# axiom_beta_plugin_module_1xUSB30_v0_2_r1.net
KiCad netlist of a schematic drawn in EAGLE
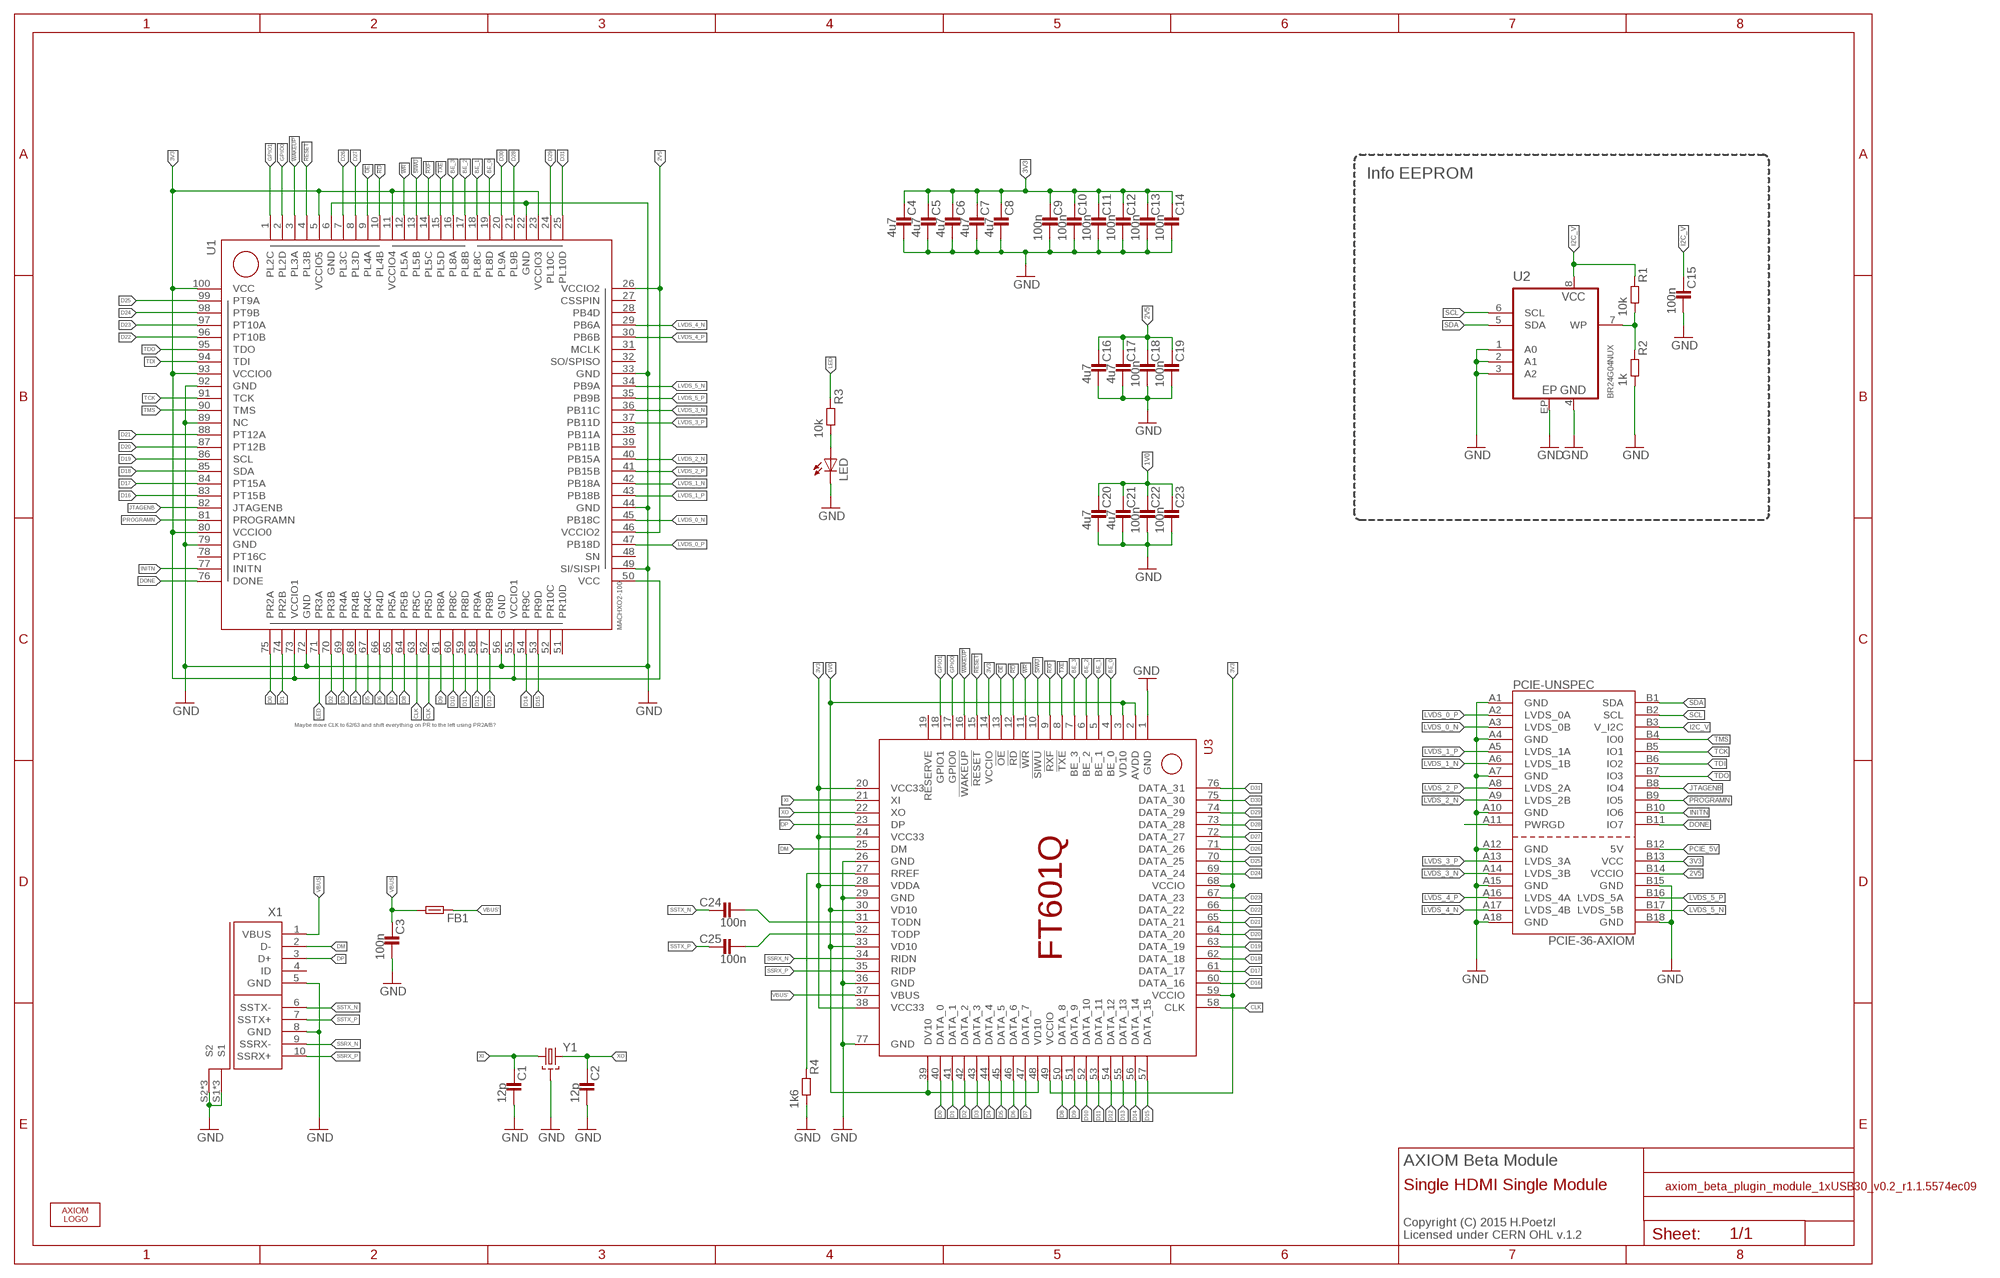
[diagram p0: schematic, sheet 1]

(export (version "E")
  (design (tool "Eeschema 10.0.6"))
  (components
    (comp (ref "C1")
      (value "12p")
      (footprint "eagle-import:0402-C")
      (libsource (lib "eagle-import") (part "C0402-C"))
    )
    (comp (ref "C2")
      (value "12p")
      (footprint "eagle-import:0402-C")
      (libsource (lib "eagle-import") (part "C0402-C"))
    )
    (comp (ref "C3")
      (value "100n")
      (footprint "eagle-import:0402-C")
      (libsource (lib "eagle-import") (part "C0402-C"))
    )
    (comp (ref "C4")
      (value "4u7")
      (footprint "eagle-import:0402-C")
      (libsource (lib "eagle-import") (part "C0402-C"))
    )
    (comp (ref "C5")
      (value "4u7")
      (footprint "eagle-import:0402-C")
      (libsource (lib "eagle-import") (part "C0402-C"))
    )
    (comp (ref "C6")
      (value "4u7")
      (footprint "eagle-import:0402-C")
      (libsource (lib "eagle-import") (part "C0402-C"))
    )
    (comp (ref "C7")
      (value "4u7")
      (footprint "eagle-import:0402-C")
      (libsource (lib "eagle-import") (part "C0402-C"))
    )
    (comp (ref "C8")
      (value "4u7")
      (footprint "eagle-import:0402-C")
      (libsource (lib "eagle-import") (part "C0402-C"))
    )
    (comp (ref "C9")
      (value "100n")
      (footprint "eagle-import:0402-C")
      (libsource (lib "eagle-import") (part "C0402-C"))
    )
    (comp (ref "C10")
      (value "100n")
      (footprint "eagle-import:0402-C")
      (libsource (lib "eagle-import") (part "C0402-C"))
    )
    (comp (ref "C11")
      (value "100n")
      (footprint "eagle-import:0402-C")
      (libsource (lib "eagle-import") (part "C0402-C"))
    )
    (comp (ref "C12")
      (value "100n")
      (footprint "eagle-import:0402-C")
      (libsource (lib "eagle-import") (part "C0402-C"))
    )
    (comp (ref "C13")
      (value "100n")
      (footprint "eagle-import:0402-C")
      (libsource (lib "eagle-import") (part "C0402-C"))
    )
    (comp (ref "C14")
      (value "100n")
      (footprint "eagle-import:0402-C")
      (libsource (lib "eagle-import") (part "C0402-C"))
    )
    (comp (ref "C15")
      (value "100n")
      (footprint "eagle-import:0402-C")
      (libsource (lib "eagle-import") (part "C0402-C"))
    )
    (comp (ref "C16")
      (value "4u7")
      (footprint "eagle-import:0402-C")
      (libsource (lib "eagle-import") (part "C0402-C"))
    )
    (comp (ref "C17")
      (value "4u7")
      (footprint "eagle-import:0402-C")
      (libsource (lib "eagle-import") (part "C0402-C"))
    )
    (comp (ref "C18")
      (value "100n")
      (footprint "eagle-import:0402-C")
      (libsource (lib "eagle-import") (part "C0402-C"))
    )
    (comp (ref "C19")
      (value "100n")
      (footprint "eagle-import:0402-C")
      (libsource (lib "eagle-import") (part "C0402-C"))
    )
    (comp (ref "C20")
      (value "4u7")
      (footprint "eagle-import:0402-C")
      (libsource (lib "eagle-import") (part "C0402-C"))
    )
    (comp (ref "C21")
      (value "4u7")
      (footprint "eagle-import:0402-C")
      (libsource (lib "eagle-import") (part "C0402-C"))
    )
    (comp (ref "C22")
      (value "100n")
      (footprint "eagle-import:0402-C")
      (libsource (lib "eagle-import") (part "C0402-C"))
    )
    (comp (ref "C23")
      (value "100n")
      (footprint "eagle-import:0402-C")
      (libsource (lib "eagle-import") (part "C0402-C"))
    )
    (comp (ref "C24")
      (value "100n")
      (footprint "eagle-import:0201-C")
      (libsource (lib "eagle-import") (part "C0201-C"))
    )
    (comp (ref "C25")
      (value "100n")
      (footprint "eagle-import:0201-C")
      (libsource (lib "eagle-import") (part "C0201-C"))
    )
    (comp (ref "FB1")
      (value "FB0402-C")
      (footprint "eagle-import:0402-C")
      (libsource (lib "eagle-import") (part "FB0402-C"))
    )
    (comp (ref "LED")
      (value "LED")
      (footprint "eagle-import:CHIPLED_0603")
      (libsource (lib "eagle-import") (part "LED"))
    )
    (comp (ref "PCIE-UNSPEC")
      (value "PCIE-36-AXIOM")
      (footprint "eagle-import:PCIE-36-AXIOM")
      (libsource (lib "eagle-import") (part "PCIE-36-AXIOM"))
    )
    (comp (ref "R1")
      (value "10k")
      (footprint "eagle-import:0402-C")
      (libsource (lib "eagle-import") (part "R0402-C"))
    )
    (comp (ref "R2")
      (value "1k")
      (footprint "eagle-import:0402-C")
      (libsource (lib "eagle-import") (part "R0402-C"))
    )
    (comp (ref "R3")
      (value "10k")
      (footprint "eagle-import:0402-B")
      (libsource (lib "eagle-import") (part "R0402-B"))
    )
    (comp (ref "R4")
      (value "1k6")
      (footprint "eagle-import:0201-C")
      (libsource (lib "eagle-import") (part "R0201-C"))
    )
    (comp (ref "U$")
      (value "AXIOM_LOGO328X50")
      (footprint "eagle-import:AXIOM_LOGO_328X50")
      (libsource (lib "eagle-import") (part "AXIOM_LOGO328X50"))
    )
    (comp (ref "U1")
      (value "MACHXO2-100")
      (footprint "eagle-import:MACHXO2-100TQFP")
      (libsource (lib "eagle-import") (part "MACHXO2-100"))
    )
    (comp (ref "U2")
      (value "BR24G04NUX")
      (footprint "eagle-import:DFN200X300X100-9N")
      (libsource (lib "eagle-import") (part "BR24G04NUX"))
    )
    (comp (ref "U3")
      (value "FT601QQFN76")
      (footprint "eagle-import:QFN76")
      (libsource (lib "eagle-import") (part "FT601QQFN76"))
    )
    (comp (ref "X1")
      (value "10_USB_3.0_2S-SMT")
      (footprint "eagle-import:MICRO-B-30-H-SMT")
      (libsource (lib "eagle-import") (part "10_USB_3.0_2S-SMT"))
    )
    (comp (ref "Y1")
      (value "SMD-4P-2G-2.0X1.6")
      (footprint "eagle-import:2.0X1.6")
      (libsource (lib "eagle-import") (part "SMD-4P-2G-2.0X1.6"))
    )
  )
  (nets
    (net (code "1") (name "/~{OE}") (class "Default")
      (node (ref "U1") (pin "9") (pinfunction "PL4A_9") (pintype "bidirectional"))
      (node (ref "U3") (pin "13") (pinfunction "~{OE}_13") (pintype "input"))
    )
    (net (code "2") (name "/~{RD}") (class "Default")
      (node (ref "U1") (pin "10") (pinfunction "PL4B_10") (pintype "bidirectional"))
      (node (ref "U3") (pin "12") (pinfunction "~{RD}_12") (pintype "input"))
    )
    (net (code "3") (name "/~{RESET}") (class "Default")
      (node (ref "U1") (pin "4") (pinfunction "PL3B_4") (pintype "bidirectional"))
      (node (ref "U3") (pin "15") (pinfunction "~{RESET}_15") (pintype "input"))
    )
    (net (code "4") (name "/~{RXF}") (class "Default")
      (node (ref "U1") (pin "14") (pinfunction "PL5C_14") (pintype "bidirectional"))
      (node (ref "U3") (pin "9") (pinfunction "~{RXF}_9") (pintype "output"))
    )
    (net (code "5") (name "/~{SIWU}") (class "Default")
      (node (ref "U1") (pin "13") (pinfunction "PL5B_13") (pintype "bidirectional"))
      (node (ref "U3") (pin "10") (pinfunction "~{SIWU}_10") (pintype "input"))
    )
    (net (code "6") (name "/~{TXE}") (class "Default")
      (node (ref "U1") (pin "15") (pinfunction "PL5D_15") (pintype "bidirectional"))
      (node (ref "U3") (pin "8") (pinfunction "~{TXE}_8") (pintype "output"))
    )
    (net (code "7") (name "/~{WAKEUP}") (class "Default")
      (node (ref "U1") (pin "3") (pinfunction "PL3A_3") (pintype "bidirectional"))
      (node (ref "U3") (pin "16") (pinfunction "~{WAKEUP}_16") (pintype "bidirectional"))
    )
    (net (code "8") (name "/~{WR}") (class "Default")
      (node (ref "U1") (pin "12") (pinfunction "PL5A_12") (pintype "bidirectional"))
      (node (ref "U3") (pin "11") (pinfunction "~{WR}_11") (pintype "input"))
    )
    (net (code "9") (name "1V0") (class "Default")
      (node (ref "C20") (pin "1") (pinfunction "1_1") (pintype "passive"))
      (node (ref "C21") (pin "1") (pinfunction "1_1") (pintype "passive"))
      (node (ref "C22") (pin "1") (pinfunction "1_1") (pintype "passive"))
      (node (ref "C23") (pin "1") (pinfunction "1_1") (pintype "passive"))
      (node (ref "U3") (pin "2") (pinfunction "AVDD_2") (pintype "power_in"))
      (node (ref "U3") (pin "3") (pinfunction "VD10_3") (pintype "power_in"))
      (node (ref "U3") (pin "30") (pinfunction "VD10_30") (pintype "power_in"))
      (node (ref "U3") (pin "33") (pinfunction "VD10_33") (pintype "power_in"))
      (node (ref "U3") (pin "39") (pinfunction "DV10_39") (pintype "power_in"))
      (node (ref "U3") (pin "48") (pinfunction "VD10_48") (pintype "power_in"))
    )
    (net (code "10") (name "2V5") (class "Default")
      (node (ref "C16") (pin "1") (pinfunction "1_1") (pintype "passive"))
      (node (ref "C17") (pin "1") (pinfunction "1_1") (pintype "passive"))
      (node (ref "C18") (pin "1") (pinfunction "1_1") (pintype "passive"))
      (node (ref "C19") (pin "1") (pinfunction "1_1") (pintype "passive"))
      (node (ref "PCIE-UNSPEC") (pin "B14") (pinfunction "VCCIO_B14") (pintype "passive"))
      (node (ref "U1") (pin "26") (pinfunction "VCCIO2_26") (pintype "power_in"))
      (node (ref "U1") (pin "46") (pinfunction "VCCIO2_46") (pintype "power_in"))
    )
    (net (code "11") (name "3V3") (class "Default")
      (node (ref "C10") (pin "1") (pinfunction "1_1") (pintype "passive"))
      (node (ref "C11") (pin "1") (pinfunction "1_1") (pintype "passive"))
      (node (ref "C12") (pin "1") (pinfunction "1_1") (pintype "passive"))
      (node (ref "C13") (pin "1") (pinfunction "1_1") (pintype "passive"))
      (node (ref "C14") (pin "1") (pinfunction "1_1") (pintype "passive"))
      (node (ref "C4") (pin "1") (pinfunction "1_1") (pintype "passive"))
      (node (ref "C5") (pin "1") (pinfunction "1_1") (pintype "passive"))
      (node (ref "C6") (pin "1") (pinfunction "1_1") (pintype "passive"))
      (node (ref "C7") (pin "1") (pinfunction "1_1") (pintype "passive"))
      (node (ref "C8") (pin "1") (pinfunction "1_1") (pintype "passive"))
      (node (ref "C9") (pin "1") (pinfunction "1_1") (pintype "passive"))
      (node (ref "PCIE-UNSPEC") (pin "B13") (pinfunction "VCC_B13") (pintype "passive"))
      (node (ref "U1") (pin "100") (pinfunction "VCC_100") (pintype "power_in"))
      (node (ref "U1") (pin "11") (pinfunction "VCCIO4_11") (pintype "power_in"))
      (node (ref "U1") (pin "23") (pinfunction "VCCIO3_23") (pintype "power_in"))
      (node (ref "U1") (pin "5") (pinfunction "VCCIO5_5") (pintype "power_in"))
      (node (ref "U1") (pin "50") (pinfunction "VCC_50") (pintype "power_in"))
      (node (ref "U1") (pin "55") (pinfunction "VCCIO1_55") (pintype "power_in"))
      (node (ref "U1") (pin "73") (pinfunction "VCCIO1_73") (pintype "power_in"))
      (node (ref "U1") (pin "80") (pinfunction "VCCIO0_80") (pintype "power_in"))
      (node (ref "U1") (pin "93") (pinfunction "VCCIO0_93") (pintype "power_in"))
      (node (ref "U3") (pin "14") (pinfunction "VCCIO_14") (pintype "power_in"))
      (node (ref "U3") (pin "20") (pinfunction "VCC33_20") (pintype "power_in"))
      (node (ref "U3") (pin "24") (pinfunction "VCC33_24") (pintype "power_in"))
      (node (ref "U3") (pin "28") (pinfunction "VDDA_28") (pintype "bidirectional"))
      (node (ref "U3") (pin "38") (pinfunction "VCC33_38") (pintype "power_in"))
      (node (ref "U3") (pin "49") (pinfunction "VCCIO_49") (pintype "power_in"))
      (node (ref "U3") (pin "59") (pinfunction "VCCIO_59") (pintype "power_in"))
      (node (ref "U3") (pin "68") (pinfunction "VCCIO_68") (pintype "power_in"))
    )
    (net (code "12") (name "BE_0") (class "Default")
      (node (ref "U1") (pin "19") (pinfunction "PL8D_19") (pintype "bidirectional"))
      (node (ref "U3") (pin "4") (pinfunction "BE_0_4") (pintype "bidirectional"))
    )
    (net (code "13") (name "BE_1") (class "Default")
      (node (ref "U1") (pin "18") (pinfunction "PL8C_18") (pintype "bidirectional"))
      (node (ref "U3") (pin "5") (pinfunction "BE_1_5") (pintype "bidirectional"))
    )
    (net (code "14") (name "BE_2") (class "Default")
      (node (ref "U1") (pin "17") (pinfunction "PL8B_17") (pintype "bidirectional"))
      (node (ref "U3") (pin "6") (pinfunction "BE_2_6") (pintype "bidirectional"))
    )
    (net (code "15") (name "BE_3") (class "Default")
      (node (ref "U1") (pin "16") (pinfunction "PL8A_16") (pintype "bidirectional"))
      (node (ref "U3") (pin "7") (pinfunction "BE_3_7") (pintype "bidirectional"))
    )
    (net (code "16") (name "CLK") (class "Default")
      (node (ref "U1") (pin "62") (pinfunction "PR5D_62") (pintype "bidirectional"))
      (node (ref "U1") (pin "63") (pinfunction "PR5C_63") (pintype "bidirectional"))
      (node (ref "U3") (pin "58") (pinfunction "CLK_58") (pintype "output"))
    )
    (net (code "17") (name "D0") (class "Default")
      (node (ref "U1") (pin "75") (pinfunction "PR2A_75") (pintype "bidirectional"))
      (node (ref "U3") (pin "40") (pinfunction "DATA_0_40") (pintype "bidirectional"))
    )
    (net (code "18") (name "D1") (class "Default")
      (node (ref "U1") (pin "74") (pinfunction "PR2B_74") (pintype "bidirectional"))
      (node (ref "U3") (pin "41") (pinfunction "DATA_1_41") (pintype "bidirectional"))
    )
    (net (code "19") (name "D2") (class "Default")
      (node (ref "U1") (pin "70") (pinfunction "PR3B_70") (pintype "bidirectional"))
      (node (ref "U3") (pin "42") (pinfunction "DATA_2_42") (pintype "bidirectional"))
    )
    (net (code "20") (name "D3") (class "Default")
      (node (ref "U1") (pin "69") (pinfunction "PR4A_69") (pintype "bidirectional"))
      (node (ref "U3") (pin "43") (pinfunction "DATA_3_43") (pintype "bidirectional"))
    )
    (net (code "21") (name "D4") (class "Default")
      (node (ref "U1") (pin "68") (pinfunction "PR4B_68") (pintype "bidirectional"))
      (node (ref "U3") (pin "44") (pinfunction "DATA_4_44") (pintype "bidirectional"))
    )
    (net (code "22") (name "D5") (class "Default")
      (node (ref "U1") (pin "67") (pinfunction "PR4C_67") (pintype "bidirectional"))
      (node (ref "U3") (pin "45") (pinfunction "DATA_5_45") (pintype "bidirectional"))
    )
    (net (code "23") (name "D6") (class "Default")
      (node (ref "U1") (pin "66") (pinfunction "PR4D_66") (pintype "bidirectional"))
      (node (ref "U3") (pin "46") (pinfunction "DATA_6_46") (pintype "bidirectional"))
    )
    (net (code "24") (name "D7") (class "Default")
      (node (ref "U1") (pin "65") (pinfunction "PR5A_65") (pintype "bidirectional"))
      (node (ref "U3") (pin "47") (pinfunction "DATA_7_47") (pintype "bidirectional"))
    )
    (net (code "25") (name "D8") (class "Default")
      (node (ref "U1") (pin "64") (pinfunction "PR5B_64") (pintype "bidirectional"))
      (node (ref "U3") (pin "50") (pinfunction "DATA_8_50") (pintype "bidirectional"))
    )
    (net (code "26") (name "D9") (class "Default")
      (node (ref "U1") (pin "61") (pinfunction "PR8A_61") (pintype "bidirectional"))
      (node (ref "U3") (pin "51") (pinfunction "DATA_9_51") (pintype "bidirectional"))
    )
    (net (code "27") (name "D10") (class "Default")
      (node (ref "U1") (pin "60") (pinfunction "PR8C_60") (pintype "bidirectional"))
      (node (ref "U3") (pin "52") (pinfunction "DATA_10_52") (pintype "bidirectional"))
    )
    (net (code "28") (name "D11") (class "Default")
      (node (ref "U1") (pin "59") (pinfunction "PR8D_59") (pintype "bidirectional"))
      (node (ref "U3") (pin "53") (pinfunction "DATA_11_53") (pintype "bidirectional"))
    )
    (net (code "29") (name "D12") (class "Default")
      (node (ref "U1") (pin "58") (pinfunction "PR9A_58") (pintype "bidirectional"))
      (node (ref "U3") (pin "54") (pinfunction "DATA_12_54") (pintype "bidirectional"))
    )
    (net (code "30") (name "D13") (class "Default")
      (node (ref "U1") (pin "57") (pinfunction "PR9B_57") (pintype "bidirectional"))
      (node (ref "U3") (pin "55") (pinfunction "DATA_13_55") (pintype "bidirectional"))
    )
    (net (code "31") (name "D14") (class "Default")
      (node (ref "U1") (pin "54") (pinfunction "PR9C_54") (pintype "bidirectional"))
      (node (ref "U3") (pin "56") (pinfunction "DATA_14_56") (pintype "bidirectional"))
    )
    (net (code "32") (name "D15") (class "Default")
      (node (ref "U1") (pin "53") (pinfunction "PR9D_53") (pintype "bidirectional"))
      (node (ref "U3") (pin "57") (pinfunction "DATA_15_57") (pintype "bidirectional"))
    )
    (net (code "33") (name "D16") (class "Default")
      (node (ref "U1") (pin "83") (pinfunction "PT15B_83") (pintype "bidirectional"))
      (node (ref "U3") (pin "60") (pinfunction "DATA_16_60") (pintype "bidirectional"))
    )
    (net (code "34") (name "D17") (class "Default")
      (node (ref "U1") (pin "84") (pinfunction "PT15A_84") (pintype "bidirectional"))
      (node (ref "U3") (pin "61") (pinfunction "DATA_17_61") (pintype "bidirectional"))
    )
    (net (code "35") (name "D18") (class "Default")
      (node (ref "U1") (pin "85") (pinfunction "SDA_85") (pintype "bidirectional"))
      (node (ref "U3") (pin "62") (pinfunction "DATA_18_62") (pintype "bidirectional"))
    )
    (net (code "36") (name "D19") (class "Default")
      (node (ref "U1") (pin "86") (pinfunction "SCL_86") (pintype "bidirectional"))
      (node (ref "U3") (pin "63") (pinfunction "DATA_19_63") (pintype "bidirectional"))
    )
    (net (code "37") (name "D20") (class "Default")
      (node (ref "U1") (pin "87") (pinfunction "PT12B_87") (pintype "bidirectional"))
      (node (ref "U3") (pin "64") (pinfunction "DATA_20_64") (pintype "bidirectional"))
    )
    (net (code "38") (name "D21") (class "Default")
      (node (ref "U1") (pin "88") (pinfunction "PT12A_88") (pintype "bidirectional"))
      (node (ref "U3") (pin "65") (pinfunction "DATA_21_65") (pintype "bidirectional"))
    )
    (net (code "39") (name "D22") (class "Default")
      (node (ref "U1") (pin "96") (pinfunction "PT10B_96") (pintype "bidirectional"))
      (node (ref "U3") (pin "66") (pinfunction "DATA_22_66") (pintype "bidirectional"))
    )
    (net (code "40") (name "D23") (class "Default")
      (node (ref "U1") (pin "97") (pinfunction "PT10A_97") (pintype "bidirectional"))
      (node (ref "U3") (pin "67") (pinfunction "DATA_23_67") (pintype "bidirectional"))
    )
    (net (code "41") (name "D24") (class "Default")
      (node (ref "U1") (pin "98") (pinfunction "PT9B_98") (pintype "bidirectional"))
      (node (ref "U3") (pin "69") (pinfunction "DATA_24_69") (pintype "bidirectional"))
    )
    (net (code "42") (name "D25") (class "Default")
      (node (ref "U1") (pin "99") (pinfunction "PT9A_99") (pintype "bidirectional"))
      (node (ref "U3") (pin "70") (pinfunction "DATA_25_70") (pintype "bidirectional"))
    )
    (net (code "43") (name "D26") (class "Default")
      (node (ref "U1") (pin "7") (pinfunction "PL3C_7") (pintype "bidirectional"))
      (node (ref "U3") (pin "71") (pinfunction "DATA_26_71") (pintype "bidirectional"))
    )
    (net (code "44") (name "D27") (class "Default")
      (node (ref "U1") (pin "8") (pinfunction "PL3D_8") (pintype "bidirectional"))
      (node (ref "U3") (pin "72") (pinfunction "DATA_27_72") (pintype "bidirectional"))
    )
    (net (code "45") (name "D28") (class "Default")
      (node (ref "U1") (pin "21") (pinfunction "PL9B_21") (pintype "bidirectional"))
      (node (ref "U3") (pin "73") (pinfunction "DATA_28_73") (pintype "bidirectional"))
    )
    (net (code "46") (name "D29") (class "Default")
      (node (ref "U1") (pin "24") (pinfunction "PL10C_24") (pintype "bidirectional"))
      (node (ref "U3") (pin "74") (pinfunction "DATA_29_74") (pintype "bidirectional"))
    )
    (net (code "47") (name "D30") (class "Default")
      (node (ref "U1") (pin "20") (pinfunction "PL9A_20") (pintype "bidirectional"))
      (node (ref "U3") (pin "75") (pinfunction "DATA_30_75") (pintype "bidirectional"))
    )
    (net (code "48") (name "D31") (class "Default")
      (node (ref "U1") (pin "25") (pinfunction "PL10D_25") (pintype "bidirectional"))
      (node (ref "U3") (pin "76") (pinfunction "DATA_31_76") (pintype "bidirectional"))
    )
    (net (code "49") (name "DM") (class "Default")
      (node (ref "U3") (pin "25") (pinfunction "DM_25") (pintype "bidirectional"))
      (node (ref "X1") (pin "2") (pinfunction "D-_2") (pintype "passive"))
    )
    (net (code "50") (name "DONE") (class "Default")
      (node (ref "PCIE-UNSPEC") (pin "B11") (pinfunction "IO7_B11") (pintype "passive"))
      (node (ref "U1") (pin "76") (pinfunction "DONE_76") (pintype "bidirectional"))
    )
    (net (code "51") (name "DP") (class "Default")
      (node (ref "U3") (pin "23") (pinfunction "DP_23") (pintype "bidirectional"))
      (node (ref "X1") (pin "3") (pinfunction "D+_3") (pintype "passive"))
    )
    (net (code "52") (name "GND") (class "Default")
      (node (ref "C1") (pin "2") (pinfunction "2_2") (pintype "passive"))
      (node (ref "C10") (pin "2") (pinfunction "2_2") (pintype "passive"))
      (node (ref "C11") (pin "2") (pinfunction "2_2") (pintype "passive"))
      (node (ref "C12") (pin "2") (pinfunction "2_2") (pintype "passive"))
      (node (ref "C13") (pin "2") (pinfunction "2_2") (pintype "passive"))
      (node (ref "C14") (pin "2") (pinfunction "2_2") (pintype "passive"))
      (node (ref "C15") (pin "2") (pinfunction "2_2") (pintype "passive"))
      (node (ref "C16") (pin "2") (pinfunction "2_2") (pintype "passive"))
      (node (ref "C17") (pin "2") (pinfunction "2_2") (pintype "passive"))
      (node (ref "C18") (pin "2") (pinfunction "2_2") (pintype "passive"))
      (node (ref "C19") (pin "2") (pinfunction "2_2") (pintype "passive"))
      (node (ref "C2") (pin "2") (pinfunction "2_2") (pintype "passive"))
      (node (ref "C20") (pin "2") (pinfunction "2_2") (pintype "passive"))
      (node (ref "C21") (pin "2") (pinfunction "2_2") (pintype "passive"))
      (node (ref "C22") (pin "2") (pinfunction "2_2") (pintype "passive"))
      (node (ref "C23") (pin "2") (pinfunction "2_2") (pintype "passive"))
      (node (ref "C3") (pin "2") (pinfunction "2_2") (pintype "passive"))
      (node (ref "C4") (pin "2") (pinfunction "2_2") (pintype "passive"))
      (node (ref "C5") (pin "2") (pinfunction "2_2") (pintype "passive"))
      (node (ref "C6") (pin "2") (pinfunction "2_2") (pintype "passive"))
      (node (ref "C7") (pin "2") (pinfunction "2_2") (pintype "passive"))
      (node (ref "C8") (pin "2") (pinfunction "2_2") (pintype "passive"))
      (node (ref "C9") (pin "2") (pinfunction "2_2") (pintype "passive"))
      (node (ref "LED") (pin "C") (pinfunction "C_C") (pintype "passive"))
      (node (ref "PCIE-UNSPEC") (pin "A1") (pinfunction "GND_A1") (pintype "passive"))
      (node (ref "PCIE-UNSPEC") (pin "A10") (pinfunction "GND_A10") (pintype "passive"))
      (node (ref "PCIE-UNSPEC") (pin "A12") (pinfunction "GND_A12") (pintype "passive"))
      (node (ref "PCIE-UNSPEC") (pin "A15") (pinfunction "GND_A15") (pintype "passive"))
      (node (ref "PCIE-UNSPEC") (pin "A18") (pinfunction "GND_A18") (pintype "passive"))
      (node (ref "PCIE-UNSPEC") (pin "A4") (pinfunction "GND_A4") (pintype "passive"))
      (node (ref "PCIE-UNSPEC") (pin "A7") (pinfunction "GND_A7") (pintype "passive"))
      (node (ref "PCIE-UNSPEC") (pin "B15") (pinfunction "GND_B15") (pintype "passive"))
      (node (ref "PCIE-UNSPEC") (pin "B18") (pinfunction "GND_B18") (pintype "passive"))
      (node (ref "R2") (pin "2") (pinfunction "2_2") (pintype "passive"))
      (node (ref "R4") (pin "2") (pinfunction "2_2") (pintype "passive"))
      (node (ref "U1") (pin "22") (pinfunction "GND_22") (pintype "power_in"))
      (node (ref "U1") (pin "33") (pinfunction "GND_33") (pintype "power_in"))
      (node (ref "U1") (pin "44") (pinfunction "GND_44") (pintype "power_in"))
      (node (ref "U1") (pin "49") (pinfunction "SI/SISPI_49") (pintype "bidirectional"))
      (node (ref "U1") (pin "56") (pinfunction "GND_56") (pintype "power_in"))
      (node (ref "U1") (pin "6") (pinfunction "GND_6") (pintype "power_in"))
      (node (ref "U1") (pin "72") (pinfunction "GND_72") (pintype "power_in"))
      (node (ref "U1") (pin "79") (pinfunction "GND_79") (pintype "power_in"))
      (node (ref "U1") (pin "89") (pinfunction "NC_89") (pintype "bidirectional"))
      (node (ref "U1") (pin "92") (pinfunction "GND_92") (pintype "power_in"))
      (node (ref "U2") (pin "1") (pinfunction "A0_1") (pintype "input"))
      (node (ref "U2") (pin "2") (pinfunction "A1_2") (pintype "input"))
      (node (ref "U2") (pin "3") (pinfunction "A2_3") (pintype "input"))
      (node (ref "U2") (pin "4") (pinfunction "GND_4") (pintype "passive"))
      (node (ref "U2") (pin "EP") (pinfunction "EP_EP") (pintype "passive"))
      (node (ref "U3") (pin "1") (pinfunction "GND_1") (pintype "power_in"))
      (node (ref "U3") (pin "26") (pinfunction "GND_26") (pintype "power_in"))
      (node (ref "U3") (pin "29") (pinfunction "GND_29") (pintype "power_in"))
      (node (ref "U3") (pin "36") (pinfunction "GND_36") (pintype "power_in"))
      (node (ref "U3") (pin "77") (pinfunction "GND_77") (pintype "power_in"))
      (node (ref "X1") (pin "5") (pinfunction "GND_5") (pintype "passive"))
      (node (ref "X1") (pin "8") (pinfunction "GND_8") (pintype "passive"))
      (node (ref "X1") (pin "S1") (pinfunction "S1_S1") (pintype "passive"))
      (node (ref "X1") (pin "S2") (pinfunction "S2_S2") (pintype "passive"))
      (node (ref "X1") (pin "Z1") (pinfunction "S1_Z1") (pintype "passive"))
      (node (ref "X1") (pin "Z2") (pinfunction "S1_Z2") (pintype "passive"))
      (node (ref "X1") (pin "Z3") (pinfunction "S2_Z3") (pintype "passive"))
      (node (ref "X1") (pin "Z4") (pinfunction "S2_Z4") (pintype "passive"))
      (node (ref "Y1") (pin "2") (pinfunction "GND_2") (pintype "power_in"))
      (node (ref "Y1") (pin "4") (pinfunction "GND_4") (pintype "power_in"))
    )
    (net (code "53") (name "GPIO0") (class "Default")
      (node (ref "U1") (pin "2") (pinfunction "PL2D_2") (pintype "bidirectional"))
      (node (ref "U3") (pin "17") (pinfunction "GPIO0_17") (pintype "bidirectional"))
    )
    (net (code "54") (name "GPIO1") (class "Default")
      (node (ref "U1") (pin "1") (pinfunction "PL2C_1") (pintype "bidirectional"))
      (node (ref "U3") (pin "18") (pinfunction "GPIO1_18") (pintype "bidirectional"))
    )
    (net (code "55") (name "I2C_V") (class "Default")
      (node (ref "C15") (pin "1") (pinfunction "1_1") (pintype "passive"))
      (node (ref "PCIE-UNSPEC") (pin "B3") (pinfunction "V_I2C_B3") (pintype "passive"))
      (node (ref "R1") (pin "1") (pinfunction "1_1") (pintype "passive"))
      (node (ref "U2") (pin "8") (pinfunction "VCC_8") (pintype "power_in"))
    )
    (net (code "56") (name "INITN") (class "Default")
      (node (ref "PCIE-UNSPEC") (pin "B10") (pinfunction "IO6_B10") (pintype "passive"))
      (node (ref "U1") (pin "77") (pinfunction "INITN_77") (pintype "bidirectional"))
    )
    (net (code "57") (name "JTAGENB") (class "Default")
      (node (ref "PCIE-UNSPEC") (pin "B8") (pinfunction "IO4_B8") (pintype "passive"))
      (node (ref "U1") (pin "82") (pinfunction "JTAGENB_82") (pintype "bidirectional"))
    )
    (net (code "58") (name "LED") (class "Default")
      (node (ref "R3") (pin "1") (pinfunction "1_1") (pintype "passive"))
      (node (ref "U1") (pin "71") (pinfunction "PR3A_71") (pintype "bidirectional"))
    )
    (net (code "59") (name "LVDS_0_N") (class "Default")
      (node (ref "PCIE-UNSPEC") (pin "A3") (pinfunction "LVDS_0B_A3") (pintype "passive"))
      (node (ref "U1") (pin "45") (pinfunction "PB18C_45") (pintype "bidirectional"))
    )
    (net (code "60") (name "LVDS_0_P") (class "Default")
      (node (ref "PCIE-UNSPEC") (pin "A2") (pinfunction "LVDS_0A_A2") (pintype "passive"))
      (node (ref "U1") (pin "47") (pinfunction "PB18D_47") (pintype "bidirectional"))
    )
    (net (code "61") (name "LVDS_1_N") (class "Default")
      (node (ref "PCIE-UNSPEC") (pin "A6") (pinfunction "LVDS_1B_A6") (pintype "passive"))
      (node (ref "U1") (pin "42") (pinfunction "PB18A_42") (pintype "bidirectional"))
    )
    (net (code "62") (name "LVDS_1_P") (class "Default")
      (node (ref "PCIE-UNSPEC") (pin "A5") (pinfunction "LVDS_1A_A5") (pintype "passive"))
      (node (ref "U1") (pin "43") (pinfunction "PB18B_43") (pintype "bidirectional"))
    )
    (net (code "63") (name "LVDS_2_N") (class "Default")
      (node (ref "PCIE-UNSPEC") (pin "A9") (pinfunction "LVDS_2B_A9") (pintype "passive"))
      (node (ref "U1") (pin "40") (pinfunction "PB15A_40") (pintype "bidirectional"))
    )
    (net (code "64") (name "LVDS_2_P") (class "Default")
      (node (ref "PCIE-UNSPEC") (pin "A8") (pinfunction "LVDS_2A_A8") (pintype "passive"))
      (node (ref "U1") (pin "41") (pinfunction "PB15B_41") (pintype "bidirectional"))
    )
    (net (code "65") (name "LVDS_3_N") (class "Default")
      (node (ref "PCIE-UNSPEC") (pin "A14") (pinfunction "LVDS_3B_A14") (pintype "passive"))
      (node (ref "U1") (pin "36") (pinfunction "PB11C_36") (pintype "bidirectional"))
    )
    (net (code "66") (name "LVDS_3_P") (class "Default")
      (node (ref "PCIE-UNSPEC") (pin "A13") (pinfunction "LVDS_3A_A13") (pintype "passive"))
      (node (ref "U1") (pin "37") (pinfunction "PB11D_37") (pintype "bidirectional"))
    )
    (net (code "67") (name "LVDS_4_N") (class "Default")
      (node (ref "PCIE-UNSPEC") (pin "A17") (pinfunction "LVDS_4B_A17") (pintype "passive"))
      (node (ref "U1") (pin "29") (pinfunction "PB6A_29") (pintype "bidirectional"))
    )
    (net (code "68") (name "LVDS_4_P") (class "Default")
      (node (ref "PCIE-UNSPEC") (pin "A16") (pinfunction "LVDS_4A_A16") (pintype "passive"))
      (node (ref "U1") (pin "30") (pinfunction "PB6B_30") (pintype "bidirectional"))
    )
    (net (code "69") (name "LVDS_5_N") (class "Default")
      (node (ref "PCIE-UNSPEC") (pin "B17") (pinfunction "LVDS_5B_B17") (pintype "passive"))
      (node (ref "U1") (pin "34") (pinfunction "PB9A_34") (pintype "bidirectional"))
    )
    (net (code "70") (name "LVDS_5_P") (class "Default")
      (node (ref "PCIE-UNSPEC") (pin "B16") (pinfunction "LVDS_5A_B16") (pintype "passive"))
      (node (ref "U1") (pin "35") (pinfunction "PB9B_35") (pintype "bidirectional"))
    )
    (net (code "71") (name "Net-(LED-PadA)") (class "Default")
      (node (ref "LED") (pin "A") (pinfunction "A_A") (pintype "passive"))
      (node (ref "R3") (pin "2") (pinfunction "2_2") (pintype "passive"))
    )
    (net (code "72") (name "Net-(U2-WP)") (class "Default")
      (node (ref "R1") (pin "2") (pinfunction "2_2") (pintype "passive"))
      (node (ref "R2") (pin "1") (pinfunction "1_1") (pintype "passive"))
      (node (ref "U2") (pin "7") (pinfunction "WP_7") (pintype "input"))
    )
    (net (code "73") (name "Net-(U3-RREF)") (class "Default")
      (node (ref "R4") (pin "1") (pinfunction "1_1") (pintype "passive"))
      (node (ref "U3") (pin "27") (pinfunction "RREF_27") (pintype "input"))
    )
    (net (code "74") (name "Net-(U3-TODN)") (class "Default")
      (node (ref "C24") (pin "2") (pinfunction "2_2") (pintype "passive"))
      (node (ref "U3") (pin "31") (pinfunction "TODN_31") (pintype "output"))
    )
    (net (code "75") (name "Net-(U3-TODP)") (class "Default")
      (node (ref "C25") (pin "2") (pinfunction "2_2") (pintype "passive"))
      (node (ref "U3") (pin "32") (pinfunction "TODP_32") (pintype "output"))
    )
    (net (code "76") (name "PCIE_5V") (class "Default")
      (node (ref "PCIE-UNSPEC") (pin "B12") (pinfunction "5V_B12") (pintype "passive"))
    )
    (net (code "77") (name "PROGRAMN") (class "Default")
      (node (ref "PCIE-UNSPEC") (pin "B9") (pinfunction "IO5_B9") (pintype "passive"))
      (node (ref "U1") (pin "81") (pinfunction "PROGRAMN_81") (pintype "bidirectional"))
    )
    (net (code "78") (name "SCL") (class "Default")
      (node (ref "PCIE-UNSPEC") (pin "B2") (pinfunction "SCL_B2") (pintype "passive"))
      (node (ref "U2") (pin "6") (pinfunction "SCL_6") (pintype "input"))
    )
    (net (code "79") (name "SDA") (class "Default")
      (node (ref "PCIE-UNSPEC") (pin "B1") (pinfunction "SDA_B1") (pintype "passive"))
      (node (ref "U2") (pin "5") (pinfunction "SDA_5") (pintype "bidirectional"))
    )
    (net (code "80") (name "SSRX_N") (class "Default")
      (node (ref "U3") (pin "34") (pinfunction "RIDN_34") (pintype "input"))
      (node (ref "X1") (pin "9") (pinfunction "SSRX-_9") (pintype "passive"))
    )
    (net (code "81") (name "SSRX_P") (class "Default")
      (node (ref "U3") (pin "35") (pinfunction "RIDP_35") (pintype "input"))
      (node (ref "X1") (pin "10") (pinfunction "SSRX+_10") (pintype "passive"))
    )
    (net (code "82") (name "SSTX_N") (class "Default")
      (node (ref "C24") (pin "1") (pinfunction "1_1") (pintype "passive"))
      (node (ref "X1") (pin "6") (pinfunction "SSTX-_6") (pintype "passive"))
    )
    (net (code "83") (name "SSTX_P") (class "Default")
      (node (ref "C25") (pin "1") (pinfunction "1_1") (pintype "passive"))
      (node (ref "X1") (pin "7") (pinfunction "SSTX+_7") (pintype "passive"))
    )
    (net (code "84") (name "TCK") (class "Default")
      (node (ref "PCIE-UNSPEC") (pin "B5") (pinfunction "IO1_B5") (pintype "passive"))
      (node (ref "U1") (pin "91") (pinfunction "TCK_91") (pintype "bidirectional"))
    )
    (net (code "85") (name "TDI") (class "Default")
      (node (ref "PCIE-UNSPEC") (pin "B6") (pinfunction "IO2_B6") (pintype "passive"))
      (node (ref "U1") (pin "94") (pinfunction "TDI_94") (pintype "bidirectional"))
    )
    (net (code "86") (name "TDO") (class "Default")
      (node (ref "PCIE-UNSPEC") (pin "B7") (pinfunction "IO3_B7") (pintype "passive"))
      (node (ref "U1") (pin "95") (pinfunction "TDO_95") (pintype "bidirectional"))
    )
    (net (code "87") (name "TMS") (class "Default")
      (node (ref "PCIE-UNSPEC") (pin "B4") (pinfunction "IO0_B4") (pintype "passive"))
      (node (ref "U1") (pin "90") (pinfunction "TMS_90") (pintype "bidirectional"))
    )
    (net (code "88") (name "VBUS") (class "Default")
      (node (ref "C3") (pin "1") (pinfunction "1_1") (pintype "passive"))
      (node (ref "FB1") (pin "2") (pinfunction "2_2") (pintype "passive"))
      (node (ref "X1") (pin "1") (pinfunction "VBUS_1") (pintype "passive"))
    )
    (net (code "89") (name "VBUS'") (class "Default")
      (node (ref "FB1") (pin "1") (pinfunction "1_1") (pintype "passive"))
      (node (ref "U3") (pin "37") (pinfunction "VBUS_37") (pintype "power_in"))
    )
    (net (code "90") (name "XI") (class "Default")
      (node (ref "C1") (pin "1") (pinfunction "1_1") (pintype "passive"))
      (node (ref "U3") (pin "21") (pinfunction "XI_21") (pintype "input"))
      (node (ref "Y1") (pin "1") (pinfunction "1_1") (pintype "passive"))
    )
    (net (code "91") (name "XO") (class "Default")
      (node (ref "C2") (pin "1") (pinfunction "1_1") (pintype "passive"))
      (node (ref "U3") (pin "22") (pinfunction "XO_22") (pintype "output"))
      (node (ref "Y1") (pin "3") (pinfunction "2_3") (pintype "passive"))
    )
    (net (code "92") (name "unconnected-(PCIE-UNSPEC-PWRGD-PadA11)") (class "Default")
      (node (ref "PCIE-UNSPEC") (pin "A11") (pinfunction "PWRGD_A11") (pintype "passive"))
    )
    (net (code "93") (name "unconnected-(U1-CSSPIN-Pad27)") (class "Default")
      (node (ref "U1") (pin "27") (pinfunction "CSSPIN_27") (pintype "bidirectional"))
    )
    (net (code "94") (name "unconnected-(U1-MCLK-Pad31)") (class "Default")
      (node (ref "U1") (pin "31") (pinfunction "MCLK_31") (pintype "bidirectional"))
    )
    (net (code "95") (name "unconnected-(U1-PB4D-Pad28)") (class "Default")
      (node (ref "U1") (pin "28") (pinfunction "PB4D_28") (pintype "bidirectional"))
    )
    (net (code "96") (name "unconnected-(U1-PB11A-Pad38)") (class "Default")
      (node (ref "U1") (pin "38") (pinfunction "PB11A_38") (pintype "bidirectional"))
    )
    (net (code "97") (name "unconnected-(U1-PB11B-Pad39)") (class "Default")
      (node (ref "U1") (pin "39") (pinfunction "PB11B_39") (pintype "bidirectional"))
    )
    (net (code "98") (name "unconnected-(U1-PR10C-Pad52)") (class "Default")
      (node (ref "U1") (pin "52") (pinfunction "PR10C_52") (pintype "bidirectional"))
    )
    (net (code "99") (name "unconnected-(U1-PR10D-Pad51)") (class "Default")
      (node (ref "U1") (pin "51") (pinfunction "PR10D_51") (pintype "bidirectional"))
    )
    (net (code "100") (name "unconnected-(U1-PT16C-Pad78)") (class "Default")
      (node (ref "U1") (pin "78") (pinfunction "PT16C_78") (pintype "bidirectional"))
    )
    (net (code "101") (name "unconnected-(U1-SN-Pad48)") (class "Default")
      (node (ref "U1") (pin "48") (pinfunction "SN_48") (pintype "bidirectional"))
    )
    (net (code "102") (name "unconnected-(U1-SO{slash}SPISO-Pad32)") (class "Default")
      (node (ref "U1") (pin "32") (pinfunction "SO/SPISO_32") (pintype "bidirectional"))
    )
    (net (code "103") (name "unconnected-(U3-RESERVE-Pad19)") (class "Default")
      (node (ref "U3") (pin "19") (pinfunction "RESERVE_19") (pintype "bidirectional"))
    )
    (net (code "104") (name "unconnected-(X1-ID-Pad4)") (class "Default")
      (node (ref "X1") (pin "4") (pinfunction "ID_4") (pintype "passive"))
    )
  )
)
